# ST_SYS_Board_Config.net
KiCad netlist of a schematic drawn in Altium Designer
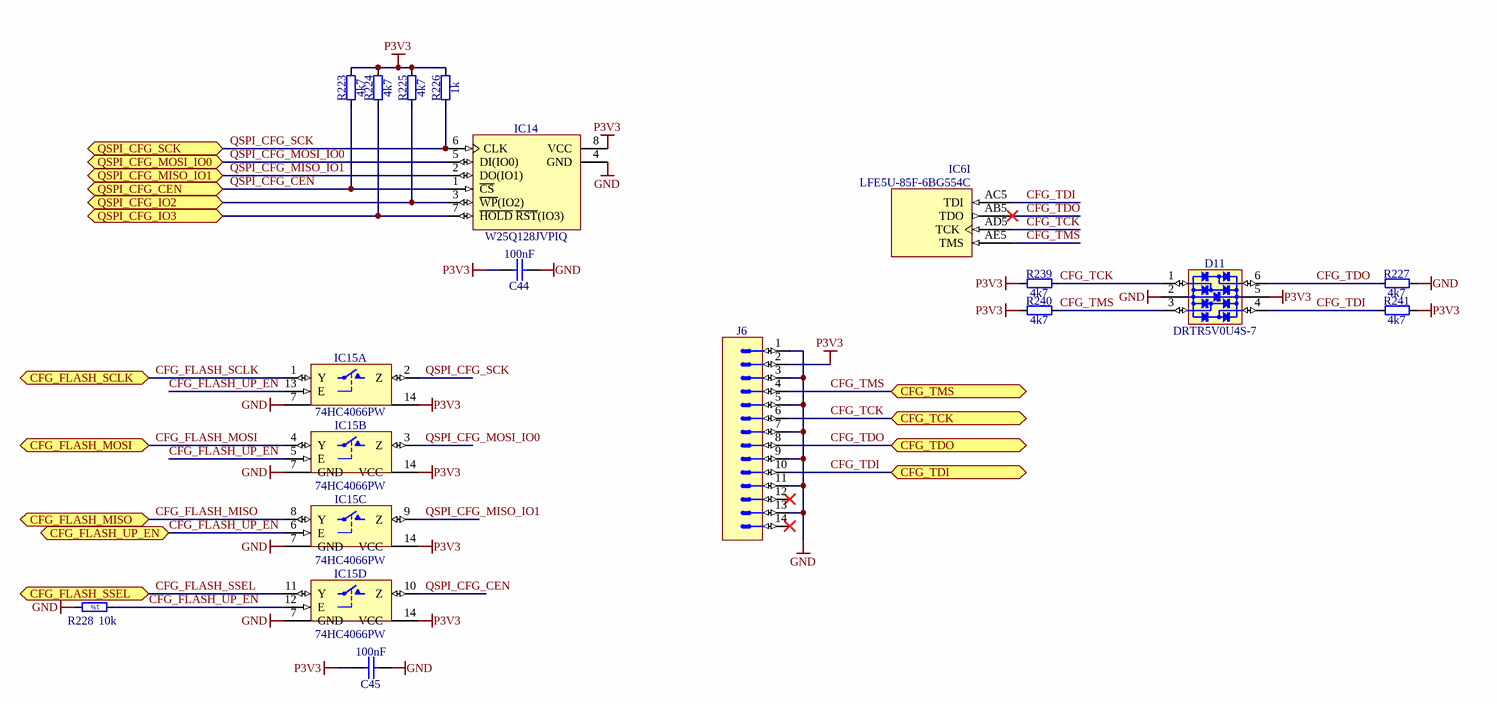
[diagram p0: ST_SYS_Board_Config.schdoc]

(export (version "E")
  (design (tool "Eeschema 10.0.6"))
  (components
    (comp (ref "C44")
      (value "100nF")
      (footprint "CAPC1005X55N")
      (description "Non-polarised capacitor")
      (fields
        (field (name "PART NUMBER") "CC0402_100NF_16V_10%_X5R")
        (field (name "VOLTAGE") "16V")
        (field (name "AUTHOR") "CERN DEM JLC")
      )
      (libsource (lib "Capacitors") (part "Capacitor - non polarized"))
    )
    (comp (ref "C45")
      (value "100nF")
      (footprint "CAPC1005X55N")
      (description "Non-polarised capacitor")
      (fields
        (field (name "PART NUMBER") "CC0402_100NF_16V_10%_X5R")
        (field (name "VOLTAGE") "16V")
        (field (name "AUTHOR") "CERN DEM JLC")
      )
      (libsource (lib "Capacitors") (part "Capacitor - non polarized"))
    )
    (comp (ref "D11")
      (value "DRTR5V0U4S-7")
      (footprint "SOT65P210X110-6N")
      (description "Integrated Quad Ultra-Low Capacitance ESD Protection")
      (fields (field (name "MANUFACTURER") "DIODES") (field (name "AUTHOR") "GK"))
      (libsource (lib "Diodes") (part "D_TVS_DRTR5V0U4S-7"))
    )
    (comp (ref "IC6")
      (value "LFE5U-85F-6BG554C")
      (footprint "BGA554C80P26X26_2300X2300X176")
      (fields (field (name "MANUFACTURER") "LATTICE SEMICONDUCTOR") (field (name "AUTHOR") "CERN DEM HF"))
      (libsource (lib "ICs And Semiconductors") (part "LFE5U-85F-6BG554C"))
    )
    (comp (ref "IC14")
      (value "W25Q128JVPIQ")
      (footprint "SON127P600X500X80-9N-R345X435")
      (description "128M-bit Serial Flash Memory with uniform 4KB sectors and Dual/Quad SPI and QPI")
      (fields (field (name "MANUFACTURER") "WINBOND") (field (name "AUTHOR") "CERN DEM BC"))
      (libsource (lib "ICs And Semiconductors") (part "W25Q128JVPIQ"))
    )
    (comp (ref "IC15")
      (value "74HC4066PW")
      (footprint "SOP65P640X110-14N")
      (fields (field (name "MANUFACTURER") "NXP SEMICONDUCTORS") (field (name "AUTHOR") "CERN DEM JLC"))
      (libsource (lib "ICs And Semiconductors") (part "4066"))
    )
    (comp (ref "J6")
      (value "Milli-Grid™")
      (footprint "MOLEX_87832-1420")
      (description "Connector 14 Male")
      (fields
        (field (name "PART NUMBER") "MOLEX_87832-1420")
        (field (name "MANUFACTURER") "MOLEX")
        (field (name "AUTHOR") "CERN DEM JLC")
      )
      (libsource (lib "Connectors") (part "Connector 14 Male"))
    )
    (comp (ref "R223")
      (value "4k7")
      (footprint "RESC1005X40N")
      (description "Resistor - 1%")
      (fields
        (field (name "PART NUMBER") "R0402_4K7_1%_0.0625W_100PPM")
        (field (name "POWER") "0.0625W")
        (field (name "AUTHOR") "CERN DEM JLC")
      )
      (libsource (lib "Resistors") (part "Resistor - 1%"))
    )
    (comp (ref "R224")
      (value "4k7")
      (footprint "RESC1005X40N")
      (description "Resistor - 1%")
      (fields
        (field (name "PART NUMBER") "R0402_4K7_1%_0.0625W_100PPM")
        (field (name "POWER") "0.0625W")
        (field (name "AUTHOR") "CERN DEM JLC")
      )
      (libsource (lib "Resistors") (part "Resistor - 1%"))
    )
    (comp (ref "R225")
      (value "4k7")
      (footprint "RESC1005X40N")
      (description "Resistor - 1%")
      (fields
        (field (name "PART NUMBER") "R0402_4K7_1%_0.0625W_100PPM")
        (field (name "POWER") "0.0625W")
        (field (name "AUTHOR") "CERN DEM JLC")
      )
      (libsource (lib "Resistors") (part "Resistor - 1%"))
    )
    (comp (ref "R226")
      (value "1k")
      (footprint "RESC1005X40N")
      (description "Resistor - 1%")
      (fields
        (field (name "PART NUMBER") "R0402_1K_1%_0.0625W_100PPM")
        (field (name "POWER") "0.0625W")
        (field (name "AUTHOR") "CERN DEM JLC")
      )
      (libsource (lib "Resistors") (part "Resistor - 1%"))
    )
    (comp (ref "R227")
      (value "4k7")
      (footprint "RESC1005X40N")
      (description "Resistor - 1%")
      (fields
        (field (name "PART NUMBER") "R0402_4K7_1%_0.0625W_100PPM")
        (field (name "POWER") "0.0625W")
        (field (name "AUTHOR") "CERN DEM JLC")
      )
      (libsource (lib "Resistors") (part "Resistor - 1%"))
    )
    (comp (ref "R228")
      (value "10k")
      (footprint "RESC1005X40N")
      (description "Resistor - 1%")
      (fields
        (field (name "PART NUMBER") "R0402_10K_1%_0.0625W_100PPM")
        (field (name "POWER") "0.0625W")
        (field (name "AUTHOR") "CERN DEM JLC")
      )
      (libsource (lib "Resistors") (part "Resistor - 1%"))
    )
    (comp (ref "R239")
      (value "4k7")
      (footprint "RESC1005X40N")
      (description "Resistor - 1%")
      (fields
        (field (name "PART NUMBER") "R0402_4K7_1%_0.0625W_100PPM")
        (field (name "POWER") "0.0625W")
        (field (name "AUTHOR") "CERN DEM JLC")
      )
      (libsource (lib "Resistors") (part "Resistor - 1%"))
    )
    (comp (ref "R240")
      (value "4k7")
      (footprint "RESC1005X40N")
      (description "Resistor - 1%")
      (fields
        (field (name "PART NUMBER") "R0402_4K7_1%_0.0625W_100PPM")
        (field (name "POWER") "0.0625W")
        (field (name "AUTHOR") "CERN DEM JLC")
      )
      (libsource (lib "Resistors") (part "Resistor - 1%"))
    )
    (comp (ref "R241")
      (value "4k7")
      (footprint "RESC1005X40N")
      (description "Resistor - 1%")
      (fields
        (field (name "PART NUMBER") "R0402_4K7_1%_0.0625W_100PPM")
        (field (name "POWER") "0.0625W")
        (field (name "AUTHOR") "CERN DEM JLC")
      )
      (libsource (lib "Resistors") (part "Resistor - 1%"))
    )
  )
  (nets
    (net (code "1") (name "/CFG_FLASH_MISO") (class "Default")
      (node (ref "IC15") (pin "8") (pinfunction "Y_8") (pintype "bidirectional"))
    )
    (net (code "2") (name "/CFG_FLASH_MOSI") (class "Default")
      (node (ref "IC15") (pin "4") (pinfunction "Y_4") (pintype "bidirectional"))
    )
    (net (code "3") (name "/CFG_FLASH_SCLK") (class "Default")
      (node (ref "IC15") (pin "1") (pinfunction "Y_1") (pintype "bidirectional"))
    )
    (net (code "4") (name "/CFG_FLASH_SSEL") (class "Default")
      (node (ref "IC15") (pin "11") (pinfunction "Y_11") (pintype "bidirectional"))
    )
    (net (code "5") (name "/CFG_FLASH_UP_EN") (class "Default")
      (node (ref "IC15") (pin "12") (pinfunction "E_12") (pintype "input"))
      (node (ref "IC15") (pin "13") (pinfunction "E_13") (pintype "input"))
      (node (ref "IC15") (pin "5") (pinfunction "E_5") (pintype "input"))
      (node (ref "IC15") (pin "6") (pinfunction "E_6") (pintype "input"))
      (node (ref "R228") (pin "1") (pinfunction "1_1") (pintype "passive"))
    )
    (net (code "6") (name "/CFG_TCK") (class "Default")
      (node (ref "D11") (pin "1") (pinfunction "I/O1_1") (pintype "bidirectional"))
      (node (ref "IC6") (pin "AD5") (pinfunction "TCK_AD5") (pintype "input"))
      (node (ref "J6") (pin "6") (pinfunction "6_6") (pintype "bidirectional"))
      (node (ref "R239") (pin "2") (pinfunction "2_2") (pintype "passive"))
    )
    (net (code "7") (name "/CFG_TDI") (class "Default")
      (node (ref "D11") (pin "4") (pinfunction "I/O3_4") (pintype "bidirectional"))
      (node (ref "IC6") (pin "AC5") (pinfunction "TDI_AC5") (pintype "input"))
      (node (ref "J6") (pin "10") (pinfunction "10_10") (pintype "bidirectional"))
      (node (ref "R241") (pin "1") (pinfunction "1_1") (pintype "passive"))
    )
    (net (code "8") (name "/CFG_TDO") (class "Default")
      (node (ref "D11") (pin "6") (pinfunction "I/O4_6") (pintype "bidirectional"))
      (node (ref "IC6") (pin "AB5") (pinfunction "TDO_AB5") (pintype "output"))
      (node (ref "J6") (pin "8") (pinfunction "8_8") (pintype "bidirectional"))
      (node (ref "R227") (pin "1") (pinfunction "1_1") (pintype "passive"))
    )
    (net (code "9") (name "/CFG_TMS") (class "Default")
      (node (ref "D11") (pin "3") (pinfunction "I/O2_3") (pintype "bidirectional"))
      (node (ref "IC6") (pin "AE5") (pinfunction "TMS_AE5") (pintype "input"))
      (node (ref "J6") (pin "4") (pinfunction "4_4") (pintype "bidirectional"))
      (node (ref "R240") (pin "2") (pinfunction "2_2") (pintype "passive"))
    )
    (net (code "10") (name "/QSPI_CFG_CEN") (class "Default")
      (node (ref "IC14") (pin "1") (pinfunction "~{CS}_1") (pintype "input"))
      (node (ref "IC15") (pin "10") (pinfunction "Z_10") (pintype "bidirectional"))
      (node (ref "R223") (pin "1") (pinfunction "1_1") (pintype "passive"))
    )
    (net (code "11") (name "/QSPI_CFG_IO2") (class "Default")
      (node (ref "IC14") (pin "3") (pinfunction "~{WP}(IO2)_3") (pintype "bidirectional"))
      (node (ref "R225") (pin "1") (pinfunction "1_1") (pintype "passive"))
    )
    (net (code "12") (name "/QSPI_CFG_IO3") (class "Default")
      (node (ref "IC14") (pin "7") (pinfunction "~{HOLD}_~{RST}(IO3)_7") (pintype "bidirectional"))
      (node (ref "R224") (pin "1") (pinfunction "1_1") (pintype "passive"))
    )
    (net (code "13") (name "/QSPI_CFG_MISO_IO1") (class "Default")
      (node (ref "IC14") (pin "2") (pinfunction "DO(IO1)_2") (pintype "bidirectional"))
      (node (ref "IC15") (pin "9") (pinfunction "Z_9") (pintype "bidirectional"))
    )
    (net (code "14") (name "/QSPI_CFG_MOSI_IO0") (class "Default")
      (node (ref "IC14") (pin "5") (pinfunction "DI(IO0)_5") (pintype "bidirectional"))
      (node (ref "IC15") (pin "3") (pinfunction "Z_3") (pintype "bidirectional"))
    )
    (net (code "15") (name "/QSPI_CFG_SCK") (class "Default")
      (node (ref "IC14") (pin "6") (pinfunction "CLK_6") (pintype "input"))
      (node (ref "IC15") (pin "2") (pinfunction "Z_2") (pintype "bidirectional"))
      (node (ref "R226") (pin "1") (pinfunction "1_1") (pintype "passive"))
    )
    (net (code "16") (name "GND") (class "Default")
      (node (ref "C44") (pin "1") (pinfunction "1_1") (pintype "passive"))
      (node (ref "C45") (pin "1") (pinfunction "1_1") (pintype "passive"))
      (node (ref "D11") (pin "2") (pinfunction "GND_2") (pintype "power_in"))
      (node (ref "IC14") (pin "4") (pinfunction "GND_4") (pintype "power_in"))
      (node (ref "IC15") (pin "7") (pinfunction "GND_7") (pintype "power_in"))
      (node (ref "J6") (pin "1") (pinfunction "1_1") (pintype "bidirectional"))
      (node (ref "J6") (pin "11") (pinfunction "11_11") (pintype "bidirectional"))
      (node (ref "J6") (pin "13") (pinfunction "13_13") (pintype "bidirectional"))
      (node (ref "J6") (pin "3") (pinfunction "3_3") (pintype "bidirectional"))
      (node (ref "J6") (pin "5") (pinfunction "5_5") (pintype "bidirectional"))
      (node (ref "J6") (pin "7") (pinfunction "7_7") (pintype "bidirectional"))
      (node (ref "J6") (pin "9") (pinfunction "9_9") (pintype "bidirectional"))
      (node (ref "R227") (pin "2") (pinfunction "2_2") (pintype "passive"))
      (node (ref "R228") (pin "2") (pinfunction "2_2") (pintype "passive"))
    )
    (net (code "17") (name "P3V3") (class "Default")
      (node (ref "C44") (pin "2") (pinfunction "2_2") (pintype "passive"))
      (node (ref "C45") (pin "2") (pinfunction "2_2") (pintype "passive"))
      (node (ref "D11") (pin "5") (pinfunction "VBUS_5") (pintype "power_in"))
      (node (ref "IC14") (pin "8") (pinfunction "VCC_8") (pintype "power_in"))
      (node (ref "IC15") (pin "14") (pinfunction "VCC_14") (pintype "power_in"))
      (node (ref "J6") (pin "2") (pinfunction "2_2") (pintype "bidirectional"))
      (node (ref "R223") (pin "2") (pinfunction "2_2") (pintype "passive"))
      (node (ref "R224") (pin "2") (pinfunction "2_2") (pintype "passive"))
      (node (ref "R225") (pin "2") (pinfunction "2_2") (pintype "passive"))
      (node (ref "R226") (pin "2") (pinfunction "2_2") (pintype "passive"))
      (node (ref "R239") (pin "1") (pinfunction "1_1") (pintype "passive"))
      (node (ref "R240") (pin "1") (pinfunction "1_1") (pintype "passive"))
      (node (ref "R241") (pin "2") (pinfunction "2_2") (pintype "passive"))
    )
    (net (code "18") (name "unconnected-(J6-Pad12)") (class "Default")
      (node (ref "J6") (pin "12") (pinfunction "12_12") (pintype "bidirectional+no_connect"))
    )
    (net (code "19") (name "unconnected-(J6-Pad14)") (class "Default")
      (node (ref "J6") (pin "14") (pinfunction "14_14") (pintype "bidirectional+no_connect"))
    )
  )
)
